# MACHNGUYENLI.net
KiCad netlist of a schematic drawn in Altium Designer
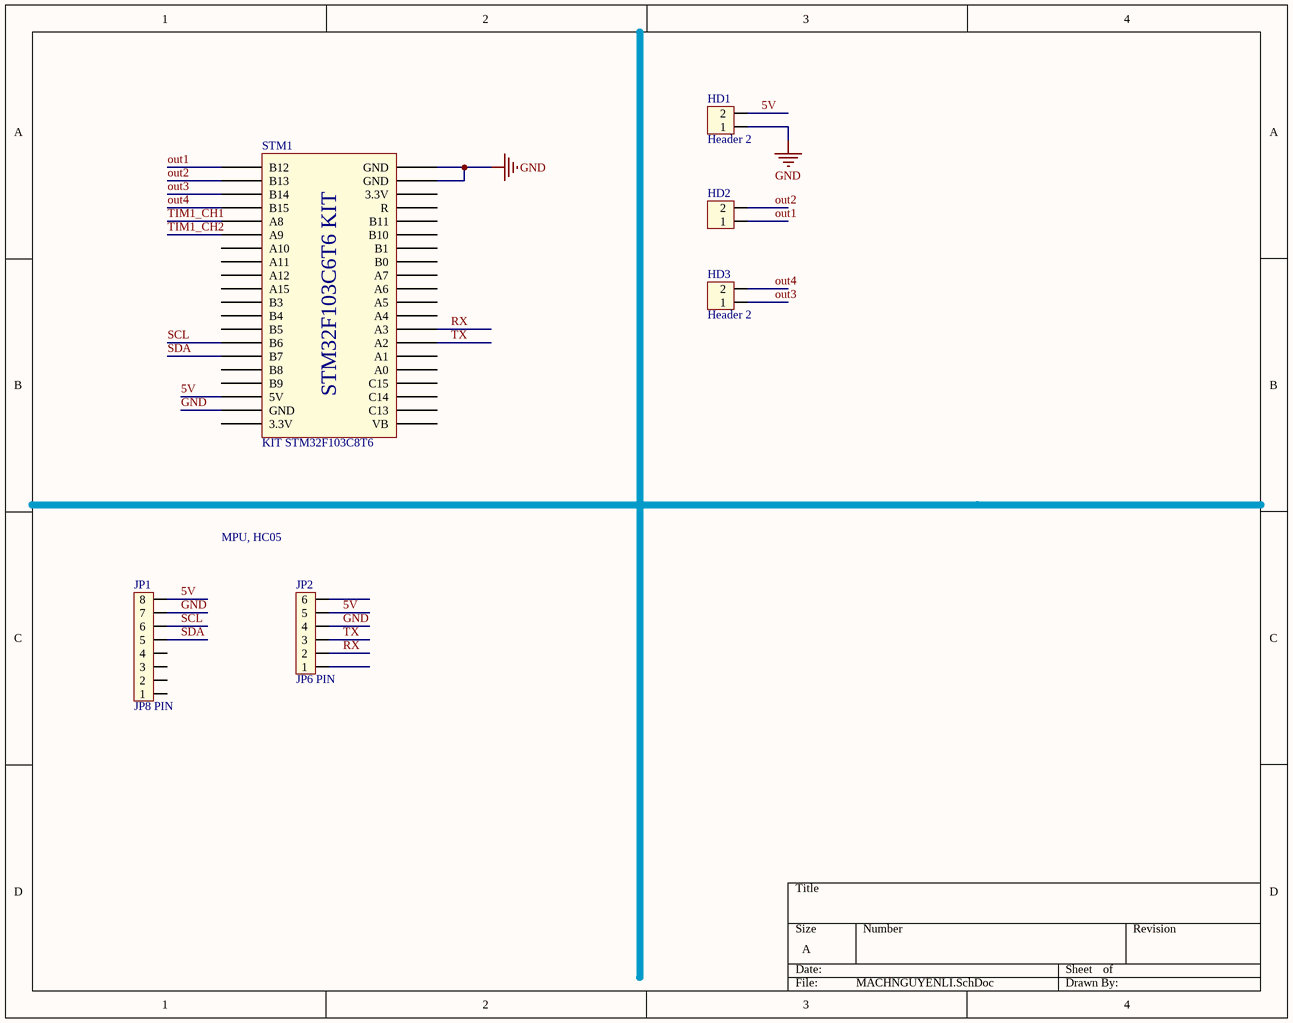
[diagram p0: MACHNGUYENLI.SchDoc]

(export (version "E")
  (design (tool "Eeschema 10.0.6"))
  (components
    (comp (ref "HD1")
      (value "Header 2")
      (footprint "HED2T")
      (description "Header 2 (Green)")
      (libsource (lib "main_mini_module") (part "Hed2"))
    )
    (comp (ref "HD2")
      (value "~")
      (footprint "HED2")
      (description "Header 2 (Green)")
      (libsource (lib "syhaunguyen") (part "Hed2"))
    )
    (comp (ref "HD3")
      (value "Header 2")
      (footprint "HED2")
      (description "Header 2 (Green)")
      (libsource (lib "syhaunguyen") (part "Hed2"))
    )
    (comp (ref "JP1") (value "JP8 PIN") (footprint "JP8") (libsource (lib "syhaunguyen") (part "JP8")))
    (comp (ref "JP2") (value "JP6 PIN") (footprint "JP6") (libsource (lib "syhaunguyen") (part "JP6")))
    (comp (ref "STM1")
      (value "KIT STM32F103C8T6")
      (footprint "STM32F103 KIT")
      (description "KIT STM32F103C8T6 Bluepill")
      (libsource (lib "main_mini_module") (part "STM32f103 Bluepill"))
    )
  )
  (nets
    (net (code "1") (name "/5V") (class "Default")
      (node (ref "HD1") (pin "2") (pinfunction "2_2") (pintype "passive"))
      (node (ref "JP1") (pin "8") (pinfunction "8_8") (pintype "passive"))
      (node (ref "JP2") (pin "5") (pinfunction "5_5") (pintype "passive"))
      (node (ref "STM1") (pin "18") (pinfunction "5V_18") (pintype "passive"))
    )
    (net (code "2") (name "/RX") (class "Default")
      (node (ref "JP2") (pin "2") (pinfunction "2_2") (pintype "passive"))
      (node (ref "STM1") (pin "28") (pinfunction "A3_28") (pintype "passive"))
    )
    (net (code "3") (name "/SCL") (class "Default")
      (node (ref "JP1") (pin "6") (pinfunction "6_6") (pintype "passive"))
      (node (ref "STM1") (pin "14") (pinfunction "B6_14") (pintype "passive"))
    )
    (net (code "4") (name "/SDA") (class "Default")
      (node (ref "JP1") (pin "5") (pinfunction "5_5") (pintype "passive"))
      (node (ref "STM1") (pin "15") (pinfunction "B7_15") (pintype "passive"))
    )
    (net (code "5") (name "/TIM1_CH1") (class "Default")
      (node (ref "STM1") (pin "5") (pinfunction "A8_5") (pintype "passive"))
    )
    (net (code "6") (name "/TIM1_CH2") (class "Default")
      (node (ref "STM1") (pin "6") (pinfunction "A9_6") (pintype "passive"))
    )
    (net (code "7") (name "/TX") (class "Default")
      (node (ref "JP2") (pin "3") (pinfunction "3_3") (pintype "passive"))
      (node (ref "STM1") (pin "27") (pinfunction "A2_27") (pintype "passive"))
    )
    (net (code "8") (name "/out1") (class "Default")
      (node (ref "HD2") (pin "1") (pinfunction "1_1") (pintype "passive"))
      (node (ref "STM1") (pin "1") (pinfunction "B12_1") (pintype "passive"))
    )
    (net (code "9") (name "/out2") (class "Default")
      (node (ref "HD2") (pin "2") (pinfunction "2_2") (pintype "passive"))
      (node (ref "STM1") (pin "2") (pinfunction "B13_2") (pintype "passive"))
    )
    (net (code "10") (name "/out3") (class "Default")
      (node (ref "HD3") (pin "1") (pinfunction "1_1") (pintype "passive"))
      (node (ref "STM1") (pin "3") (pinfunction "B14_3") (pintype "passive"))
    )
    (net (code "11") (name "/out4") (class "Default")
      (node (ref "HD3") (pin "2") (pinfunction "2_2") (pintype "passive"))
      (node (ref "STM1") (pin "4") (pinfunction "B15_4") (pintype "passive"))
    )
    (net (code "12") (name "GND") (class "Default")
      (node (ref "HD1") (pin "1") (pinfunction "1_1") (pintype "passive"))
      (node (ref "JP1") (pin "7") (pinfunction "7_7") (pintype "passive"))
      (node (ref "JP2") (pin "4") (pinfunction "4_4") (pintype "passive"))
      (node (ref "STM1") (pin "19") (pinfunction "GND_19") (pintype "passive"))
      (node (ref "STM1") (pin "39") (pinfunction "GND_39") (pintype "passive"))
      (node (ref "STM1") (pin "40") (pinfunction "GND_40") (pintype "passive"))
    )
    (net (code "13") (name "unconnected-(JP1-Pad1)") (class "Default")
      (node (ref "JP1") (pin "1") (pinfunction "1_1") (pintype "passive"))
    )
    (net (code "14") (name "unconnected-(JP1-Pad2)") (class "Default")
      (node (ref "JP1") (pin "2") (pinfunction "2_2") (pintype "passive"))
    )
    (net (code "15") (name "unconnected-(JP1-Pad3)") (class "Default")
      (node (ref "JP1") (pin "3") (pinfunction "3_3") (pintype "passive"))
    )
    (net (code "16") (name "unconnected-(JP1-Pad4)") (class "Default")
      (node (ref "JP1") (pin "4") (pinfunction "4_4") (pintype "passive"))
    )
    (net (code "17") (name "unconnected-(JP2-Pad1)") (class "Default")
      (node (ref "JP2") (pin "1") (pinfunction "1_1") (pintype "passive"))
    )
    (net (code "18") (name "unconnected-(JP2-Pad6)") (class "Default")
      (node (ref "JP2") (pin "6") (pinfunction "6_6") (pintype "passive"))
    )
    (net (code "19") (name "unconnected-(STM1-3.3V-Pad20)") (class "Default")
      (node (ref "STM1") (pin "20") (pinfunction "3.3V_20") (pintype "passive"))
    )
    (net (code "20") (name "unconnected-(STM1-3.3V-Pad38)") (class "Default")
      (node (ref "STM1") (pin "38") (pinfunction "3.3V_38") (pintype "passive"))
    )
    (net (code "21") (name "unconnected-(STM1-A0-Pad25)") (class "Default")
      (node (ref "STM1") (pin "25") (pinfunction "A0_25") (pintype "passive"))
    )
    (net (code "22") (name "unconnected-(STM1-A1-Pad26)") (class "Default")
      (node (ref "STM1") (pin "26") (pinfunction "A1_26") (pintype "passive"))
    )
    (net (code "23") (name "unconnected-(STM1-A4-Pad29)") (class "Default")
      (node (ref "STM1") (pin "29") (pinfunction "A4_29") (pintype "passive"))
    )
    (net (code "24") (name "unconnected-(STM1-A5-Pad30)") (class "Default")
      (node (ref "STM1") (pin "30") (pinfunction "A5_30") (pintype "passive"))
    )
    (net (code "25") (name "unconnected-(STM1-A6-Pad31)") (class "Default")
      (node (ref "STM1") (pin "31") (pinfunction "A6_31") (pintype "passive"))
    )
    (net (code "26") (name "unconnected-(STM1-A7-Pad32)") (class "Default")
      (node (ref "STM1") (pin "32") (pinfunction "A7_32") (pintype "passive"))
    )
    (net (code "27") (name "unconnected-(STM1-A10-Pad7)") (class "Default")
      (node (ref "STM1") (pin "7") (pinfunction "A10_7") (pintype "passive"))
    )
    (net (code "28") (name "unconnected-(STM1-A11-Pad8)") (class "Default")
      (node (ref "STM1") (pin "8") (pinfunction "A11_8") (pintype "passive"))
    )
    (net (code "29") (name "unconnected-(STM1-A12-Pad9)") (class "Default")
      (node (ref "STM1") (pin "9") (pinfunction "A12_9") (pintype "passive"))
    )
    (net (code "30") (name "unconnected-(STM1-A15-Pad10)") (class "Default")
      (node (ref "STM1") (pin "10") (pinfunction "A15_10") (pintype "passive"))
    )
    (net (code "31") (name "unconnected-(STM1-B0-Pad33)") (class "Default")
      (node (ref "STM1") (pin "33") (pinfunction "B0_33") (pintype "passive"))
    )
    (net (code "32") (name "unconnected-(STM1-B1-Pad34)") (class "Default")
      (node (ref "STM1") (pin "34") (pinfunction "B1_34") (pintype "passive"))
    )
    (net (code "33") (name "unconnected-(STM1-B3-Pad11)") (class "Default")
      (node (ref "STM1") (pin "11") (pinfunction "B3_11") (pintype "passive"))
    )
    (net (code "34") (name "unconnected-(STM1-B4-Pad12)") (class "Default")
      (node (ref "STM1") (pin "12") (pinfunction "B4_12") (pintype "passive"))
    )
    (net (code "35") (name "unconnected-(STM1-B5-Pad13)") (class "Default")
      (node (ref "STM1") (pin "13") (pinfunction "B5_13") (pintype "passive"))
    )
    (net (code "36") (name "unconnected-(STM1-B8-Pad16)") (class "Default")
      (node (ref "STM1") (pin "16") (pinfunction "B8_16") (pintype "passive"))
    )
    (net (code "37") (name "unconnected-(STM1-B9-Pad17)") (class "Default")
      (node (ref "STM1") (pin "17") (pinfunction "B9_17") (pintype "passive"))
    )
    (net (code "38") (name "unconnected-(STM1-B10-Pad35)") (class "Default")
      (node (ref "STM1") (pin "35") (pinfunction "B10_35") (pintype "passive"))
    )
    (net (code "39") (name "unconnected-(STM1-B11-Pad36)") (class "Default")
      (node (ref "STM1") (pin "36") (pinfunction "B11_36") (pintype "passive"))
    )
    (net (code "40") (name "unconnected-(STM1-C13-Pad22)") (class "Default")
      (node (ref "STM1") (pin "22") (pinfunction "C13_22") (pintype "passive"))
    )
    (net (code "41") (name "unconnected-(STM1-C14-Pad23)") (class "Default")
      (node (ref "STM1") (pin "23") (pinfunction "C14_23") (pintype "passive"))
    )
    (net (code "42") (name "unconnected-(STM1-C15-Pad24)") (class "Default")
      (node (ref "STM1") (pin "24") (pinfunction "C15_24") (pintype "passive"))
    )
    (net (code "43") (name "unconnected-(STM1-R-Pad37)") (class "Default")
      (node (ref "STM1") (pin "37") (pinfunction "R_37") (pintype "passive"))
    )
    (net (code "44") (name "unconnected-(STM1-VB-Pad21)") (class "Default")
      (node (ref "STM1") (pin "21") (pinfunction "VB_21") (pintype "passive"))
    )
  )
)
